# arduino_shield.net
KiCad netlist of a schematic drawn in EAGLE
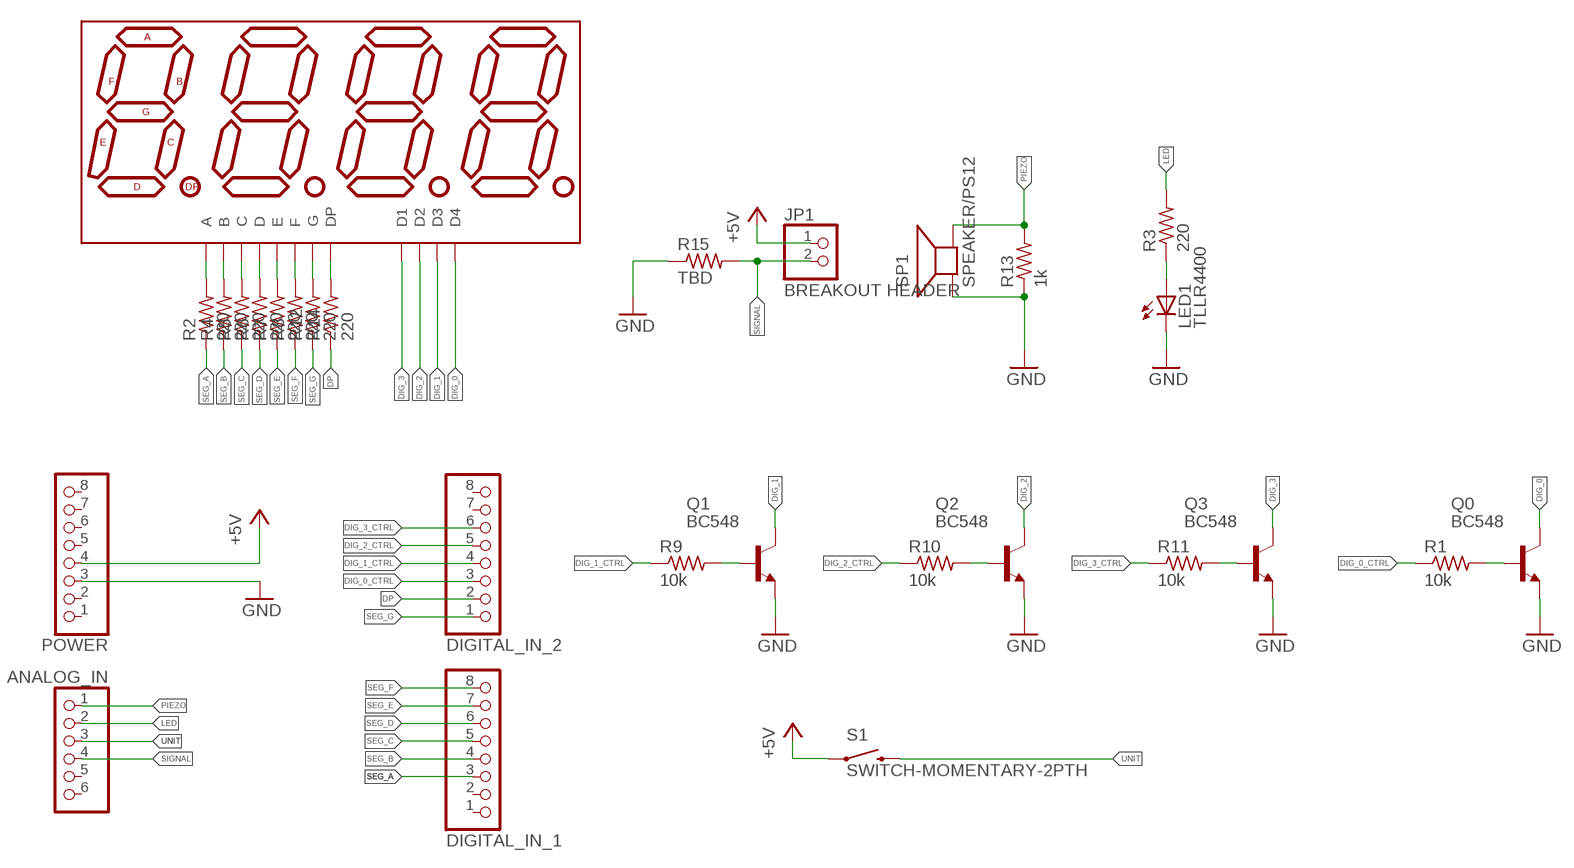
[diagram p0: schematic, sheet 1]

(export (version "E")
  (design (tool "Eeschema 10.0.6"))
  (components
    (comp (ref "ANALOG_IN")
      (value "PINHD-1X6CB")
      (footprint "eagle-import:1X06-CLEANBIG")
      (libsource (lib "eagle-import") (part "PINHD-1X6CB"))
    )
    (comp (ref "DIGITAL_IN_1")
      (value "PINHD-1X8CLEANBIG")
      (footprint "eagle-import:1X08-CLEANBIG")
      (libsource (lib "eagle-import") (part "PINHD-1X8CLEANBIG"))
    )
    (comp (ref "DIGITAL_IN_2")
      (value "PINHD-1X8CLEANBIG")
      (footprint "eagle-import:1X08-CLEANBIG")
      (libsource (lib "eagle-import") (part "PINHD-1X8CLEANBIG"))
    )
    (comp (ref "DISP1")
      (value "7-SEGMENT-4DIGIT-COUNTERPTH")
      (footprint "eagle-import:7-SEGMENT-4DIGIT-COUNTER")
      (libsource (lib "eagle-import") (part "7-SEGMENT-4DIGIT-COUNTERPTH"))
    )
    (comp (ref "JP1")
      (value "BREAKOUT HEADER")
      (footprint "eagle-import:1X02")
      (libsource (lib "eagle-import") (part "PINHD-1X2"))
    )
    (comp (ref "LED1")
      (value "TLLR4400")
      (footprint "eagle-import:LED3MM")
      (fields (field (name "MF") "VISHAY SEMICONDUCTOR"))
      (libsource (lib "eagle-import") (part "TLLR4400"))
    )
    (comp (ref "POWER")
      (value "PINHD-1X8CLEANBIG")
      (footprint "eagle-import:1X08-CLEANBIG")
      (libsource (lib "eagle-import") (part "PINHD-1X8CLEANBIG"))
    )
    (comp (ref "Q0")
      (value "BC548")
      (footprint "eagle-import:TO92-EBC")
      (libsource (lib "eagle-import") (part "BC548"))
    )
    (comp (ref "Q1")
      (value "BC548")
      (footprint "eagle-import:TO92-EBC")
      (libsource (lib "eagle-import") (part "BC548"))
    )
    (comp (ref "Q2")
      (value "BC548")
      (footprint "eagle-import:TO92-EBC")
      (libsource (lib "eagle-import") (part "BC548"))
    )
    (comp (ref "Q3")
      (value "BC548")
      (footprint "eagle-import:TO92-EBC")
      (libsource (lib "eagle-import") (part "BC548"))
    )
    (comp (ref "R1")
      (value "10k")
      (footprint "eagle-import:0207_10")
      (libsource (lib "eagle-import") (part "R-US_0207/10"))
    )
    (comp (ref "R2")
      (value "220")
      (footprint "eagle-import:0207_10")
      (libsource (lib "eagle-import") (part "R-US_0207/10"))
    )
    (comp (ref "R3")
      (value "220")
      (footprint "eagle-import:0207_10")
      (libsource (lib "eagle-import") (part "R-US_0207/10"))
    )
    (comp (ref "R4")
      (value "220")
      (footprint "eagle-import:0207_10")
      (libsource (lib "eagle-import") (part "R-US_0207/10"))
    )
    (comp (ref "R5")
      (value "220")
      (footprint "eagle-import:0207_10")
      (libsource (lib "eagle-import") (part "R-US_0207/10"))
    )
    (comp (ref "R6")
      (value "220")
      (footprint "eagle-import:0207_10")
      (libsource (lib "eagle-import") (part "R-US_0207/10"))
    )
    (comp (ref "R7")
      (value "220")
      (footprint "eagle-import:0207_10")
      (libsource (lib "eagle-import") (part "R-US_0207/10"))
    )
    (comp (ref "R8")
      (value "220")
      (footprint "eagle-import:0207_10")
      (libsource (lib "eagle-import") (part "R-US_0207/10"))
    )
    (comp (ref "R9")
      (value "10k")
      (footprint "eagle-import:0207_10")
      (libsource (lib "eagle-import") (part "R-US_0207/10"))
    )
    (comp (ref "R10")
      (value "10k")
      (footprint "eagle-import:0207_10")
      (libsource (lib "eagle-import") (part "R-US_0207/10"))
    )
    (comp (ref "R11")
      (value "10k")
      (footprint "eagle-import:0207_10")
      (libsource (lib "eagle-import") (part "R-US_0207/10"))
    )
    (comp (ref "R12")
      (value "220")
      (footprint "eagle-import:0207_10")
      (libsource (lib "eagle-import") (part "R-US_0207/10"))
    )
    (comp (ref "R13")
      (value "1k")
      (footprint "eagle-import:0207_10")
      (libsource (lib "eagle-import") (part "R-US_0207/10"))
    )
    (comp (ref "R14")
      (value "220")
      (footprint "eagle-import:0207_10")
      (libsource (lib "eagle-import") (part "R-US_0207/10"))
    )
    (comp (ref "R15")
      (value "TBD")
      (footprint "eagle-import:0207_10")
      (libsource (lib "eagle-import") (part "R-US_0207/10"))
    )
    (comp (ref "S1")
      (value "SWITCH-MOMENTARY-2PTH")
      (footprint "eagle-import:TACTILE-PTH")
      (libsource (lib "eagle-import") (part "SWITCH-MOMENTARY-2PTH"))
    )
    (comp (ref "SP1")
      (value "SPEAKER/PS12")
      (footprint "eagle-import:PS12")
      (libsource (lib "eagle-import") (part "SPEAKER/PS12"))
    )
  )
  (nets
    (net (code "1") (name "+5V") (class "Default")
      (node (ref "JP1") (pin "1") (pinfunction "1_1") (pintype "passive"))
      (node (ref "POWER") (pin "4") (pinfunction "4_4") (pintype "passive"))
      (node (ref "S1") (pin "1") (pinfunction "1_1") (pintype "passive"))
    )
    (net (code "2") (name "DIG_0") (class "Default")
      (node (ref "DISP1") (pin "6") (pinfunction "D4_6") (pintype "bidirectional"))
      (node (ref "Q0") (pin "C") (pinfunction "C_C") (pintype "passive"))
    )
    (net (code "3") (name "DIG_0_CTRL") (class "Default")
      (node (ref "DIGITAL_IN_2") (pin "3") (pinfunction "3_3") (pintype "passive"))
      (node (ref "R1") (pin "1") (pinfunction "1_1") (pintype "passive"))
    )
    (net (code "4") (name "DIG_1") (class "Default")
      (node (ref "DISP1") (pin "8") (pinfunction "D3_8") (pintype "bidirectional"))
      (node (ref "Q1") (pin "C") (pinfunction "C_C") (pintype "passive"))
    )
    (net (code "5") (name "DIG_1_CTRL") (class "Default")
      (node (ref "DIGITAL_IN_2") (pin "4") (pinfunction "4_4") (pintype "passive"))
      (node (ref "R9") (pin "1") (pinfunction "1_1") (pintype "passive"))
    )
    (net (code "6") (name "DIG_2") (class "Default")
      (node (ref "DISP1") (pin "9") (pinfunction "D2_9") (pintype "bidirectional"))
      (node (ref "Q2") (pin "C") (pinfunction "C_C") (pintype "passive"))
    )
    (net (code "7") (name "DIG_2_CTRL") (class "Default")
      (node (ref "DIGITAL_IN_2") (pin "5") (pinfunction "5_5") (pintype "passive"))
      (node (ref "R10") (pin "1") (pinfunction "1_1") (pintype "passive"))
    )
    (net (code "8") (name "DIG_3") (class "Default")
      (node (ref "DISP1") (pin "12") (pinfunction "D1_12") (pintype "bidirectional"))
      (node (ref "Q3") (pin "C") (pinfunction "C_C") (pintype "passive"))
    )
    (net (code "9") (name "DIG_3_CTRL") (class "Default")
      (node (ref "DIGITAL_IN_2") (pin "6") (pinfunction "6_6") (pintype "passive"))
      (node (ref "R11") (pin "1") (pinfunction "1_1") (pintype "passive"))
    )
    (net (code "10") (name "DP") (class "Default")
      (node (ref "DIGITAL_IN_2") (pin "2") (pinfunction "2_2") (pintype "passive"))
      (node (ref "R14") (pin "1") (pinfunction "1_1") (pintype "passive"))
    )
    (net (code "11") (name "GND") (class "Default")
      (node (ref "LED1") (pin "K") (pinfunction "C_K") (pintype "passive"))
      (node (ref "POWER") (pin "3") (pinfunction "3_3") (pintype "passive"))
      (node (ref "Q0") (pin "E") (pinfunction "E_E") (pintype "passive"))
      (node (ref "Q1") (pin "E") (pinfunction "E_E") (pintype "passive"))
      (node (ref "Q2") (pin "E") (pinfunction "E_E") (pintype "passive"))
      (node (ref "Q3") (pin "E") (pinfunction "E_E") (pintype "passive"))
      (node (ref "R13") (pin "1") (pinfunction "1_1") (pintype "passive"))
      (node (ref "R15") (pin "1") (pinfunction "1_1") (pintype "passive"))
      (node (ref "SP1") (pin "P$1") (pinfunction "+_P$1") (pintype "passive"))
    )
    (net (code "12") (name "LED") (class "Default")
      (node (ref "ANALOG_IN") (pin "2") (pinfunction "2_2") (pintype "passive"))
      (node (ref "R3") (pin "2") (pinfunction "2_2") (pintype "passive"))
    )
    (net (code "13") (name "Net-(DISP1-A)") (class "Default")
      (node (ref "DISP1") (pin "11") (pinfunction "A_11") (pintype "bidirectional"))
      (node (ref "R2") (pin "2") (pinfunction "2_2") (pintype "passive"))
    )
    (net (code "14") (name "Net-(DISP1-B)") (class "Default")
      (node (ref "DISP1") (pin "7") (pinfunction "B_7") (pintype "bidirectional"))
      (node (ref "R4") (pin "2") (pinfunction "2_2") (pintype "passive"))
    )
    (net (code "15") (name "Net-(DISP1-C)") (class "Default")
      (node (ref "DISP1") (pin "4") (pinfunction "C_4") (pintype "bidirectional"))
      (node (ref "R5") (pin "2") (pinfunction "2_2") (pintype "passive"))
    )
    (net (code "16") (name "Net-(DISP1-D)") (class "Default")
      (node (ref "DISP1") (pin "2") (pinfunction "D_2") (pintype "bidirectional"))
      (node (ref "R6") (pin "2") (pinfunction "2_2") (pintype "passive"))
    )
    (net (code "17") (name "Net-(DISP1-DP)") (class "Default")
      (node (ref "DISP1") (pin "3") (pinfunction "DP_3") (pintype "bidirectional"))
      (node (ref "R14") (pin "2") (pinfunction "2_2") (pintype "passive"))
    )
    (net (code "18") (name "Net-(DISP1-E)") (class "Default")
      (node (ref "DISP1") (pin "1") (pinfunction "E_1") (pintype "bidirectional"))
      (node (ref "R7") (pin "2") (pinfunction "2_2") (pintype "passive"))
    )
    (net (code "19") (name "Net-(DISP1-F)") (class "Default")
      (node (ref "DISP1") (pin "10") (pinfunction "F_10") (pintype "bidirectional"))
      (node (ref "R8") (pin "2") (pinfunction "2_2") (pintype "passive"))
    )
    (net (code "20") (name "Net-(DISP1-G)") (class "Default")
      (node (ref "DISP1") (pin "5") (pinfunction "G_5") (pintype "bidirectional"))
      (node (ref "R12") (pin "2") (pinfunction "2_2") (pintype "passive"))
    )
    (net (code "21") (name "Net-(LED1-PadA)") (class "Default")
      (node (ref "LED1") (pin "A") (pinfunction "A_A") (pintype "passive"))
      (node (ref "R3") (pin "1") (pinfunction "1_1") (pintype "passive"))
    )
    (net (code "22") (name "Net-(Q0-PadB)") (class "Default")
      (node (ref "Q0") (pin "B") (pinfunction "B_B") (pintype "passive"))
      (node (ref "R1") (pin "2") (pinfunction "2_2") (pintype "passive"))
    )
    (net (code "23") (name "Net-(Q1-PadB)") (class "Default")
      (node (ref "Q1") (pin "B") (pinfunction "B_B") (pintype "passive"))
      (node (ref "R9") (pin "2") (pinfunction "2_2") (pintype "passive"))
    )
    (net (code "24") (name "Net-(Q2-PadB)") (class "Default")
      (node (ref "Q2") (pin "B") (pinfunction "B_B") (pintype "passive"))
      (node (ref "R10") (pin "2") (pinfunction "2_2") (pintype "passive"))
    )
    (net (code "25") (name "Net-(Q3-PadB)") (class "Default")
      (node (ref "Q3") (pin "B") (pinfunction "B_B") (pintype "passive"))
      (node (ref "R11") (pin "2") (pinfunction "2_2") (pintype "passive"))
    )
    (net (code "26") (name "PIEZO") (class "Default")
      (node (ref "ANALOG_IN") (pin "1") (pinfunction "1_1") (pintype "passive"))
      (node (ref "R13") (pin "2") (pinfunction "2_2") (pintype "passive"))
      (node (ref "SP1") (pin "P$2") (pinfunction "-_P$2") (pintype "passive"))
    )
    (net (code "27") (name "SEG_A") (class "Default")
      (node (ref "DIGITAL_IN_1") (pin "3") (pinfunction "3_3") (pintype "passive"))
      (node (ref "R2") (pin "1") (pinfunction "1_1") (pintype "passive"))
    )
    (net (code "28") (name "SEG_B") (class "Default")
      (node (ref "DIGITAL_IN_1") (pin "4") (pinfunction "4_4") (pintype "passive"))
      (node (ref "R4") (pin "1") (pinfunction "1_1") (pintype "passive"))
    )
    (net (code "29") (name "SEG_C") (class "Default")
      (node (ref "DIGITAL_IN_1") (pin "5") (pinfunction "5_5") (pintype "passive"))
      (node (ref "R5") (pin "1") (pinfunction "1_1") (pintype "passive"))
    )
    (net (code "30") (name "SEG_D") (class "Default")
      (node (ref "DIGITAL_IN_1") (pin "6") (pinfunction "6_6") (pintype "passive"))
      (node (ref "R6") (pin "1") (pinfunction "1_1") (pintype "passive"))
    )
    (net (code "31") (name "SEG_E") (class "Default")
      (node (ref "DIGITAL_IN_1") (pin "7") (pinfunction "7_7") (pintype "passive"))
      (node (ref "R7") (pin "1") (pinfunction "1_1") (pintype "passive"))
    )
    (net (code "32") (name "SEG_F") (class "Default")
      (node (ref "DIGITAL_IN_1") (pin "8") (pinfunction "8_8") (pintype "passive"))
      (node (ref "R8") (pin "1") (pinfunction "1_1") (pintype "passive"))
    )
    (net (code "33") (name "SEG_G") (class "Default")
      (node (ref "DIGITAL_IN_2") (pin "1") (pinfunction "1_1") (pintype "passive"))
      (node (ref "R12") (pin "1") (pinfunction "1_1") (pintype "passive"))
    )
    (net (code "34") (name "SIGNAL") (class "Default")
      (node (ref "ANALOG_IN") (pin "4") (pinfunction "4_4") (pintype "passive"))
      (node (ref "JP1") (pin "2") (pinfunction "2_2") (pintype "passive"))
      (node (ref "R15") (pin "2") (pinfunction "2_2") (pintype "passive"))
    )
    (net (code "35") (name "UNIT") (class "Default")
      (node (ref "ANALOG_IN") (pin "3") (pinfunction "3_3") (pintype "passive"))
      (node (ref "S1") (pin "3") (pinfunction "2_3") (pintype "passive"))
    )
    (net (code "36") (name "unconnected-(ANALOG_IN-Pad5)") (class "Default")
      (node (ref "ANALOG_IN") (pin "5") (pinfunction "5_5") (pintype "passive"))
    )
    (net (code "37") (name "unconnected-(ANALOG_IN-Pad6)") (class "Default")
      (node (ref "ANALOG_IN") (pin "6") (pinfunction "6_6") (pintype "passive"))
    )
    (net (code "38") (name "unconnected-(DIGITAL_IN_1-Pad1)") (class "Default")
      (node (ref "DIGITAL_IN_1") (pin "1") (pinfunction "1_1") (pintype "passive"))
    )
    (net (code "39") (name "unconnected-(DIGITAL_IN_1-Pad2)") (class "Default")
      (node (ref "DIGITAL_IN_1") (pin "2") (pinfunction "2_2") (pintype "passive"))
    )
    (net (code "40") (name "unconnected-(DIGITAL_IN_2-Pad7)") (class "Default")
      (node (ref "DIGITAL_IN_2") (pin "7") (pinfunction "7_7") (pintype "passive"))
    )
    (net (code "41") (name "unconnected-(DIGITAL_IN_2-Pad8)") (class "Default")
      (node (ref "DIGITAL_IN_2") (pin "8") (pinfunction "8_8") (pintype "passive"))
    )
    (net (code "42") (name "unconnected-(POWER-Pad1)") (class "Default")
      (node (ref "POWER") (pin "1") (pinfunction "1_1") (pintype "passive"))
    )
    (net (code "43") (name "unconnected-(POWER-Pad2)") (class "Default")
      (node (ref "POWER") (pin "2") (pinfunction "2_2") (pintype "passive"))
    )
    (net (code "44") (name "unconnected-(POWER-Pad5)") (class "Default")
      (node (ref "POWER") (pin "5") (pinfunction "5_5") (pintype "passive"))
    )
    (net (code "45") (name "unconnected-(POWER-Pad6)") (class "Default")
      (node (ref "POWER") (pin "6") (pinfunction "6_6") (pintype "passive"))
    )
    (net (code "46") (name "unconnected-(POWER-Pad7)") (class "Default")
      (node (ref "POWER") (pin "7") (pinfunction "7_7") (pintype "passive"))
    )
    (net (code "47") (name "unconnected-(POWER-Pad8)") (class "Default")
      (node (ref "POWER") (pin "8") (pinfunction "8_8") (pintype "passive"))
    )
  )
)
